# NanoBud.net
KiCad netlist of a schematic drawn in EAGLE
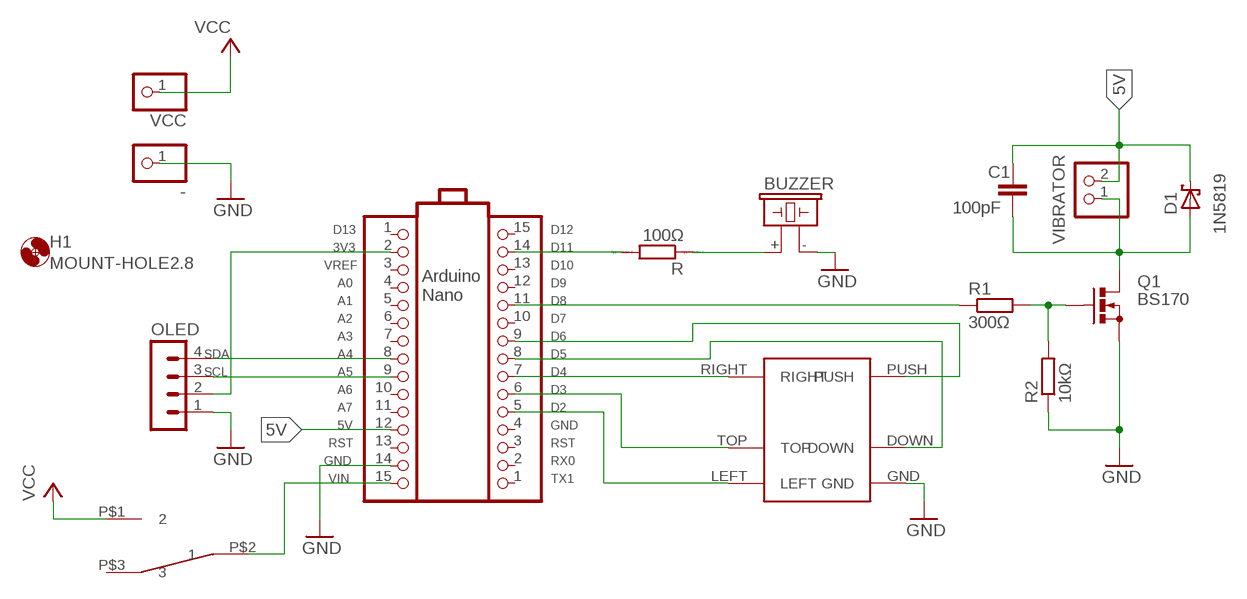
[diagram p0: schematic, sheet 1]

(export (version "E")
  (design (tool "Eeschema 10.0.6"))
  (components
    (comp (ref "-")
      (value "PINHD-1X1")
      (footprint "eagle-import:1X01")
      (libsource (lib "eagle-import") (part "PINHD-1X1"))
    )
    (comp (ref "BUZZER")
      (value "F/CM12P")
      (footprint "eagle-import:F_CM12P")
      (libsource (lib "eagle-import") (part "F/CM12P"))
    )
    (comp (ref "C1")
      (value "100pF")
      (footprint "eagle-import:C2.5-2")
      (libsource (lib "eagle-import") (part "C2.5/2"))
    )
    (comp (ref "D1")
      (value "BAT49")
      (footprint "eagle-import:DO41-10")
      (libsource (lib "eagle-import") (part "BAT49"))
    )
    (comp (ref "H1")
      (value "MOUNT-HOLE2.8")
      (footprint "eagle-import:2,8")
      (libsource (lib "eagle-import") (part "MOUNT-HOLE2.8"))
    )
    (comp (ref "OLED")
      (value "MA04-1")
      (footprint "eagle-import:MA04-1")
      (libsource (lib "eagle-import") (part "MA04-1"))
    )
    (comp (ref "Q1")
      (value "BS170")
      (footprint "eagle-import:SOT54E")
      (libsource (lib "eagle-import") (part "BS170"))
    )
    (comp (ref "R")
      (value "100Ω")
      (footprint "eagle-import:0204_7")
      (libsource (lib "eagle-import") (part "R0204/7"))
    )
    (comp (ref "R1")
      (value "300Ω")
      (footprint "eagle-import:0204_7")
      (libsource (lib "eagle-import") (part "R-EU_0204/7"))
    )
    (comp (ref "R2")
      (value "10kΩ")
      (footprint "eagle-import:0204_7")
      (libsource (lib "eagle-import") (part "R-EU_0204/7"))
    )
    (comp (ref "SV1")
      (value "PINHD-1X15")
      (footprint "eagle-import:1X15")
      (libsource (lib "eagle-import") (part "PINHD-1X15"))
    )
    (comp (ref "SV2")
      (value "PINHD-1X15")
      (footprint "eagle-import:1X15")
      (libsource (lib "eagle-import") (part "PINHD-1X15"))
    )
    (comp (ref "U$1")
      (value "SWITCHCHINOIS")
      (footprint "eagle-import:SWITCHCHINOIS")
      (libsource (lib "eagle-import") (part "SWITCHCHINOIS"))
    )
    (comp (ref "U$2")
      (value "MOMENTARYBUTTON")
      (footprint "eagle-import:MOMENTARYBUTTON")
      (libsource (lib "eagle-import") (part "MOMENTARYBUTTON"))
    )
    (comp (ref "VCC")
      (value "PINHD-1X1")
      (footprint "eagle-import:1X01")
      (libsource (lib "eagle-import") (part "PINHD-1X1"))
    )
    (comp (ref "VIBRATOR")
      (value "PINHD-1X2")
      (footprint "eagle-import:1X02")
      (libsource (lib "eagle-import") (part "PINHD-1X2"))
    )
  )
  (nets
    (net (code "1") (name "5V") (class "Default")
      (node (ref "C1") (pin "1") (pinfunction "1_1") (pintype "passive"))
      (node (ref "D1") (pin "C") (pinfunction "C_C") (pintype "passive"))
      (node (ref "SV2") (pin "12") (pinfunction "12_12") (pintype "passive"))
      (node (ref "VIBRATOR") (pin "2") (pinfunction "2_2") (pintype "passive"))
    )
    (net (code "2") (name "GND") (class "Default")
      (node (ref "-") (pin "1") (pinfunction "1_1") (pintype "passive"))
      (node (ref "BUZZER") (pin "-") (pinfunction "2_-") (pintype "passive"))
      (node (ref "OLED") (pin "1") (pinfunction "1_1") (pintype "passive"))
      (node (ref "Q1") (pin "S") (pinfunction "S_S") (pintype "passive"))
      (node (ref "R2") (pin "1") (pinfunction "1_1") (pintype "passive"))
      (node (ref "SV2") (pin "14") (pinfunction "14_14") (pintype "passive"))
      (node (ref "U$2") (pin "GND") (pinfunction "GND_GND") (pintype "bidirectional"))
    )
    (net (code "3") (name "Net-(BUZZER-1)") (class "Default")
      (node (ref "BUZZER") (pin "+") (pinfunction "1_+") (pintype "passive"))
      (node (ref "R") (pin "1") (pinfunction "1_1") (pintype "passive"))
    )
    (net (code "4") (name "Net-(C1-Pad2)") (class "Default")
      (node (ref "C1") (pin "2") (pinfunction "2_2") (pintype "passive"))
      (node (ref "D1") (pin "A") (pinfunction "A_A") (pintype "passive"))
      (node (ref "Q1") (pin "D") (pinfunction "D_D") (pintype "passive"))
      (node (ref "VIBRATOR") (pin "1") (pinfunction "1_1") (pintype "passive"))
    )
    (net (code "5") (name "Net-(OLED-Pad2)") (class "Default")
      (node (ref "OLED") (pin "2") (pinfunction "2_2") (pintype "passive"))
      (node (ref "SV2") (pin "2") (pinfunction "2_2") (pintype "passive"))
    )
    (net (code "6") (name "Net-(OLED-Pad3)") (class "Default")
      (node (ref "OLED") (pin "3") (pinfunction "3_3") (pintype "passive"))
      (node (ref "SV2") (pin "9") (pinfunction "9_9") (pintype "passive"))
    )
    (net (code "7") (name "Net-(OLED-Pad4)") (class "Default")
      (node (ref "OLED") (pin "4") (pinfunction "4_4") (pintype "passive"))
      (node (ref "SV2") (pin "8") (pinfunction "8_8") (pintype "passive"))
    )
    (net (code "8") (name "Net-(Q1-PadG)") (class "Default")
      (node (ref "Q1") (pin "G") (pinfunction "G_G") (pintype "passive"))
      (node (ref "R1") (pin "2") (pinfunction "2_2") (pintype "passive"))
      (node (ref "R2") (pin "2") (pinfunction "2_2") (pintype "passive"))
    )
    (net (code "9") (name "Net-(R-Pad2)") (class "Default")
      (node (ref "R") (pin "2") (pinfunction "2_2") (pintype "passive"))
      (node (ref "SV1") (pin "14") (pinfunction "14_14") (pintype "passive"))
    )
    (net (code "10") (name "Net-(R1-Pad1)") (class "Default")
      (node (ref "R1") (pin "1") (pinfunction "1_1") (pintype "passive"))
      (node (ref "SV1") (pin "11") (pinfunction "11_11") (pintype "passive"))
    )
    (net (code "11") (name "Net-(SV1-Pad5)") (class "Default")
      (node (ref "SV1") (pin "5") (pinfunction "5_5") (pintype "passive"))
      (node (ref "U$2") (pin "LEFT") (pinfunction "LEFT_LEFT") (pintype "bidirectional"))
    )
    (net (code "12") (name "Net-(SV1-Pad6)") (class "Default")
      (node (ref "SV1") (pin "6") (pinfunction "6_6") (pintype "passive"))
      (node (ref "U$2") (pin "TOP") (pinfunction "TOP_TOP") (pintype "bidirectional"))
    )
    (net (code "13") (name "Net-(SV1-Pad7)") (class "Default")
      (node (ref "SV1") (pin "7") (pinfunction "7_7") (pintype "passive"))
      (node (ref "U$2") (pin "RIGHT") (pinfunction "RIGHT_RIGHT") (pintype "bidirectional"))
    )
    (net (code "14") (name "Net-(SV1-Pad8)") (class "Default")
      (node (ref "SV1") (pin "8") (pinfunction "8_8") (pintype "passive"))
      (node (ref "U$2") (pin "DOWN") (pinfunction "DOWN_DOWN") (pintype "bidirectional"))
    )
    (net (code "15") (name "Net-(SV1-Pad9)") (class "Default")
      (node (ref "SV1") (pin "9") (pinfunction "9_9") (pintype "passive"))
      (node (ref "U$2") (pin "PUSH") (pinfunction "PUSH_PUSH") (pintype "bidirectional"))
    )
    (net (code "16") (name "Net-(U$1-1)") (class "Default")
      (node (ref "SV2") (pin "15") (pinfunction "15_15") (pintype "passive"))
      (node (ref "U$1") (pin "P$2") (pinfunction "1_P$2") (pintype "bidirectional"))
    )
    (net (code "17") (name "VCC") (class "Default")
      (node (ref "U$1") (pin "P$1") (pinfunction "2_P$1") (pintype "bidirectional"))
      (node (ref "VCC") (pin "1") (pinfunction "1_1") (pintype "passive"))
    )
    (net (code "18") (name "unconnected-(SV1-Pad1)") (class "Default")
      (node (ref "SV1") (pin "1") (pinfunction "1_1") (pintype "passive"))
    )
    (net (code "19") (name "unconnected-(SV1-Pad2)") (class "Default")
      (node (ref "SV1") (pin "2") (pinfunction "2_2") (pintype "passive"))
    )
    (net (code "20") (name "unconnected-(SV1-Pad3)") (class "Default")
      (node (ref "SV1") (pin "3") (pinfunction "3_3") (pintype "passive"))
    )
    (net (code "21") (name "unconnected-(SV1-Pad4)") (class "Default")
      (node (ref "SV1") (pin "4") (pinfunction "4_4") (pintype "passive"))
    )
    (net (code "22") (name "unconnected-(SV1-Pad10)") (class "Default")
      (node (ref "SV1") (pin "10") (pinfunction "10_10") (pintype "passive"))
    )
    (net (code "23") (name "unconnected-(SV1-Pad12)") (class "Default")
      (node (ref "SV1") (pin "12") (pinfunction "12_12") (pintype "passive"))
    )
    (net (code "24") (name "unconnected-(SV1-Pad13)") (class "Default")
      (node (ref "SV1") (pin "13") (pinfunction "13_13") (pintype "passive"))
    )
    (net (code "25") (name "unconnected-(SV1-Pad15)") (class "Default")
      (node (ref "SV1") (pin "15") (pinfunction "15_15") (pintype "passive"))
    )
    (net (code "26") (name "unconnected-(SV2-Pad1)") (class "Default")
      (node (ref "SV2") (pin "1") (pinfunction "1_1") (pintype "passive"))
    )
    (net (code "27") (name "unconnected-(SV2-Pad3)") (class "Default")
      (node (ref "SV2") (pin "3") (pinfunction "3_3") (pintype "passive"))
    )
    (net (code "28") (name "unconnected-(SV2-Pad4)") (class "Default")
      (node (ref "SV2") (pin "4") (pinfunction "4_4") (pintype "passive"))
    )
    (net (code "29") (name "unconnected-(SV2-Pad5)") (class "Default")
      (node (ref "SV2") (pin "5") (pinfunction "5_5") (pintype "passive"))
    )
    (net (code "30") (name "unconnected-(SV2-Pad6)") (class "Default")
      (node (ref "SV2") (pin "6") (pinfunction "6_6") (pintype "passive"))
    )
    (net (code "31") (name "unconnected-(SV2-Pad7)") (class "Default")
      (node (ref "SV2") (pin "7") (pinfunction "7_7") (pintype "passive"))
    )
    (net (code "32") (name "unconnected-(SV2-Pad10)") (class "Default")
      (node (ref "SV2") (pin "10") (pinfunction "10_10") (pintype "passive"))
    )
    (net (code "33") (name "unconnected-(SV2-Pad11)") (class "Default")
      (node (ref "SV2") (pin "11") (pinfunction "11_11") (pintype "passive"))
    )
    (net (code "34") (name "unconnected-(SV2-Pad13)") (class "Default")
      (node (ref "SV2") (pin "13") (pinfunction "13_13") (pintype "passive"))
    )
    (net (code "35") (name "unconnected-(U$1-3-PadP$3)") (class "Default")
      (node (ref "U$1") (pin "P$3") (pinfunction "3_P$3") (pintype "bidirectional"))
    )
  )
)
